# irs-v6.net
KiCad netlist of a schematic drawn in EAGLE
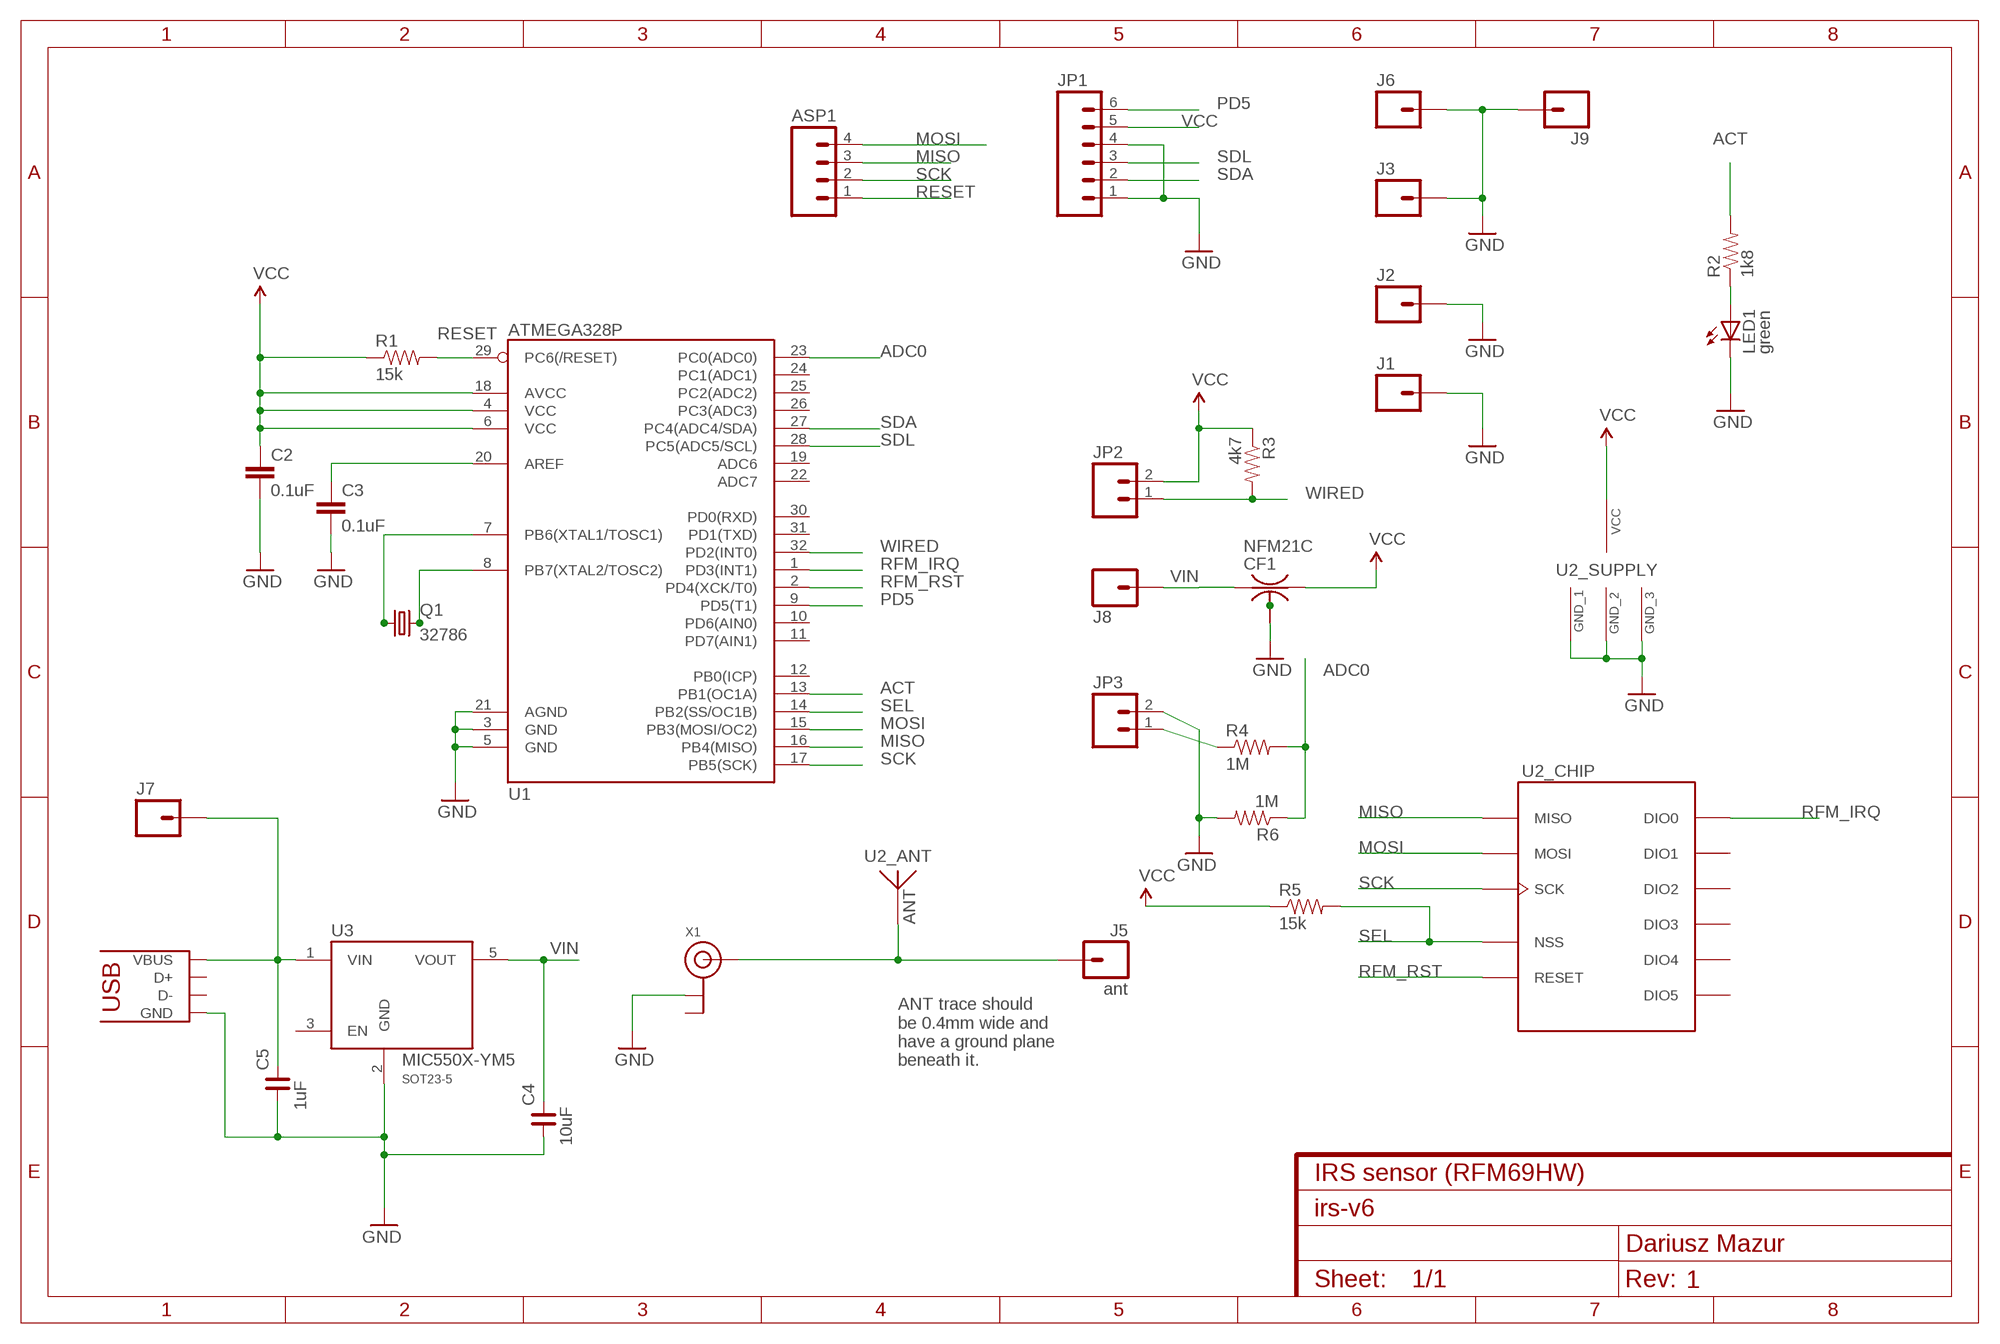
[diagram p0: schematic, sheet 1]

(export (version "E")
  (design (tool "Eeschema 10.0.6"))
  (components
    (comp (ref "ASP1")
      (value "M04NO_SILK_ALL_ROUND")
      (footprint "eagle-import:1X04_NO_SILK_ALL_ROUND")
      (libsource (lib "eagle-import") (part "M04NO_SILK_ALL_ROUND"))
    )
    (comp (ref "C2")
      (value "0.1uF")
      (footprint "eagle-import:0603-CAP")
      (libsource (lib "eagle-import") (part "0.1UF-25V(+80/-20%)(0603)"))
    )
    (comp (ref "C3")
      (value "0.1uF")
      (footprint "eagle-import:0603-CAP")
      (libsource (lib "eagle-import") (part "0.1UF-25V(+80/-20%)(0603)"))
    )
    (comp (ref "C4")
      (value "10uF")
      (footprint "eagle-import:C0805")
      (libsource (lib "eagle-import") (part "C_0805"))
    )
    (comp (ref "C5")
      (value "1uF")
      (footprint "eagle-import:C0805")
      (libsource (lib "eagle-import") (part "C_0805"))
    )
    (comp (ref "CF1")
      (value "NFM21C")
      (footprint "eagle-import:NFM21C")
      (fields (field (name "MPN") "NFM21CC102R1H3D"))
      (libsource (lib "eagle-import") (part "NFM21C"))
    )
    (comp (ref "J1")
      (value "M01PTH_NO_SILK_YES_STOP")
      (footprint "eagle-import:1X01_NO_SILK")
      (libsource (lib "eagle-import") (part "M01PTH_NO_SILK_YES_STOP"))
    )
    (comp (ref "J2")
      (value "M01PTH_NO_SILK_YES_STOP")
      (footprint "eagle-import:1X01_NO_SILK")
      (libsource (lib "eagle-import") (part "M01PTH_NO_SILK_YES_STOP"))
    )
    (comp (ref "J3")
      (value "M01PTH_NO_SILK_YES_STOP")
      (footprint "eagle-import:1X01_NO_SILK")
      (libsource (lib "eagle-import") (part "M01PTH_NO_SILK_YES_STOP"))
    )
    (comp (ref "J4")
      (value "USB-REVERSE-MICROB")
      (footprint "eagle-import:USB-MICROB")
      (libsource (lib "eagle-import") (part "USB-REVERSE-MICROB"))
    )
    (comp (ref "J5")
      (value "ant")
      (footprint "eagle-import:1X01_NO_SILK")
      (libsource (lib "eagle-import") (part "M01PTH_NO_SILK_YES_STOP"))
    )
    (comp (ref "J6")
      (value "M01PTH_NO_SILK_YES_STOP")
      (footprint "eagle-import:1X01_NO_SILK")
      (libsource (lib "eagle-import") (part "M01PTH_NO_SILK_YES_STOP"))
    )
    (comp (ref "J7")
      (value "M01PTH_NO_SILK_YES_STOP")
      (footprint "eagle-import:1X01_NO_SILK")
      (libsource (lib "eagle-import") (part "M01PTH_NO_SILK_YES_STOP"))
    )
    (comp (ref "J8")
      (value "M01PTH_NO_SILK_YES_STOP")
      (footprint "eagle-import:1X01_NO_SILK")
      (libsource (lib "eagle-import") (part "M01PTH_NO_SILK_YES_STOP"))
    )
    (comp (ref "J9")
      (value "M01PTH_NO_SILK_YES_STOP")
      (footprint "eagle-import:1X01_NO_SILK")
      (libsource (lib "eagle-import") (part "M01PTH_NO_SILK_YES_STOP"))
    )
    (comp (ref "JP1")
      (value "M06NO_SILK_FEMALE_PTH")
      (footprint "eagle-import:1X06_NO_SILK")
      (libsource (lib "eagle-import") (part "M06NO_SILK_FEMALE_PTH"))
    )
    (comp (ref "JP2")
      (value "M021X02_NO_SILK")
      (footprint "eagle-import:1X02_NO_SILK")
      (libsource (lib "eagle-import") (part "M021X02_NO_SILK"))
    )
    (comp (ref "JP3")
      (value "M021X02_NO_SILK")
      (footprint "eagle-import:1X02_NO_SILK")
      (libsource (lib "eagle-import") (part "M021X02_NO_SILK"))
    )
    (comp (ref "LED1")
      (value "green")
      (footprint "eagle-import:LED-0603")
      (libsource (lib "eagle-import") (part "LED0603"))
    )
    (comp (ref "Q1")
      (value "32786")
      (footprint "eagle-import:MC-306")
      (fields (field (name "MPN") "MC-306 60.0KHZ  100PPM ,12.5PF"))
      (libsource (lib "eagle-import") (part "MC-306"))
    )
    (comp (ref "R1")
      (value "15k")
      (footprint "eagle-import:0603-RES")
      (libsource (lib "eagle-import") (part "RESISTOR0603-RES"))
    )
    (comp (ref "R2")
      (value "1k8")
      (footprint "eagle-import:0603-RES")
      (libsource (lib "eagle-import") (part "RESISTOR0603-RES"))
    )
    (comp (ref "R3")
      (value "4k7")
      (footprint "eagle-import:0603-RES")
      (libsource (lib "eagle-import") (part "RESISTOR0603-RES"))
    )
    (comp (ref "R4")
      (value "1M")
      (footprint "eagle-import:0603-RES")
      (libsource (lib "eagle-import") (part "RESISTOR0603-RES"))
    )
    (comp (ref "R5")
      (value "15k")
      (footprint "eagle-import:0603-RES")
      (libsource (lib "eagle-import") (part "RESISTOR0603-RES"))
    )
    (comp (ref "R6")
      (value "1M")
      (footprint "eagle-import:0603-RES")
      (libsource (lib "eagle-import") (part "RESISTOR0603-RES"))
    )
    (comp (ref "U1")
      (value "ATMEGA328P")
      (footprint "eagle-import:TQFP32-08")
      (libsource (lib "eagle-import") (part "ATMEGA328_SMT"))
    )
    (comp (ref "U2")
      (value "RFM69HCW-S2")
      (footprint "eagle-import:HOPE-RF-16")
      (libsource (lib "eagle-import") (part "RFM69HCW-S2"))
    )
    (comp (ref "U3")
      (value "MIC550X-YM5")
      (footprint "eagle-import:SOT23-5-DBV")
      (libsource (lib "eagle-import") (part "MIC550X-YM5"))
    )
    (comp (ref "X1")
      (value "ANTENNA_U.FL")
      (footprint "eagle-import:U.FL")
      (libsource (lib "eagle-import") (part "ANTENNA_U.FL"))
    )
  )
  (nets
    (net (code "1") (name "/ACT") (class "Default")
      (node (ref "R2") (pin "2") (pinfunction "2_2") (pintype "passive"))
      (node (ref "U1") (pin "13") (pinfunction "PB1(OC1A)_13") (pintype "bidirectional"))
    )
    (net (code "2") (name "/ADC0") (class "Default")
      (node (ref "R4") (pin "2") (pinfunction "2_2") (pintype "passive"))
      (node (ref "R6") (pin "1") (pinfunction "1_1") (pintype "passive"))
      (node (ref "U1") (pin "23") (pinfunction "PC0(ADC0)_23") (pintype "bidirectional"))
    )
    (net (code "3") (name "/MISO") (class "Default")
      (node (ref "ASP1") (pin "3") (pinfunction "3_3") (pintype "passive"))
      (node (ref "U1") (pin "16") (pinfunction "PB4(MISO)_16") (pintype "bidirectional"))
      (node (ref "U2") (pin "MISO") (pinfunction "MISO_MISO") (pintype "input"))
    )
    (net (code "4") (name "/MOSI") (class "Default")
      (node (ref "ASP1") (pin "4") (pinfunction "4_4") (pintype "passive"))
      (node (ref "U1") (pin "15") (pinfunction "PB3(MOSI/OC2)_15") (pintype "bidirectional"))
      (node (ref "U2") (pin "MOSI") (pinfunction "MOSI_MOSI") (pintype "output"))
    )
    (net (code "5") (name "/PD5") (class "Default")
      (node (ref "JP1") (pin "6") (pinfunction "6_6") (pintype "passive"))
      (node (ref "U1") (pin "9") (pinfunction "PD5(T1)_9") (pintype "bidirectional"))
    )
    (net (code "6") (name "/RESET") (class "Default")
      (node (ref "ASP1") (pin "1") (pinfunction "1_1") (pintype "passive"))
      (node (ref "R1") (pin "2") (pinfunction "2_2") (pintype "passive"))
      (node (ref "U1") (pin "29") (pinfunction "PC6(/RESET)_29") (pintype "bidirectional"))
    )
    (net (code "7") (name "/RFM_IRQ") (class "Default")
      (node (ref "U1") (pin "1") (pinfunction "PD3(INT1)_1") (pintype "bidirectional"))
      (node (ref "U2") (pin "DIO0") (pinfunction "DIO0_DIO0") (pintype "bidirectional"))
    )
    (net (code "8") (name "/RFM_RST") (class "Default")
      (node (ref "U1") (pin "2") (pinfunction "PD4(XCK/T0)_2") (pintype "bidirectional"))
      (node (ref "U2") (pin "RESET") (pinfunction "RESET_RESET") (pintype "bidirectional"))
    )
    (net (code "9") (name "/SCK") (class "Default")
      (node (ref "ASP1") (pin "2") (pinfunction "2_2") (pintype "passive"))
      (node (ref "U1") (pin "17") (pinfunction "PB5(SCK)_17") (pintype "bidirectional"))
      (node (ref "U2") (pin "SCK") (pinfunction "SCK_SCK") (pintype "input"))
    )
    (net (code "10") (name "/SDA") (class "Default")
      (node (ref "JP1") (pin "2") (pinfunction "2_2") (pintype "passive"))
      (node (ref "U1") (pin "27") (pinfunction "PC4(ADC4/SDA)_27") (pintype "bidirectional"))
    )
    (net (code "11") (name "/SDL") (class "Default")
      (node (ref "JP1") (pin "3") (pinfunction "3_3") (pintype "passive"))
      (node (ref "U1") (pin "28") (pinfunction "PC5(ADC5/SCL)_28") (pintype "bidirectional"))
    )
    (net (code "12") (name "/SEL") (class "Default")
      (node (ref "R5") (pin "2") (pinfunction "2_2") (pintype "passive"))
      (node (ref "U1") (pin "14") (pinfunction "PB2(SS/OC1B)_14") (pintype "bidirectional"))
      (node (ref "U2") (pin "NSS") (pinfunction "NSS_NSS") (pintype "input"))
    )
    (net (code "13") (name "/VIN") (class "Default")
      (node (ref "C4") (pin "2") (pinfunction "2_2") (pintype "passive"))
      (node (ref "CF1") (pin "1") (pinfunction "1_1") (pintype "passive"))
      (node (ref "J8") (pin "1") (pinfunction "1_1") (pintype "passive"))
      (node (ref "U3") (pin "5") (pinfunction "VOUT_5") (pintype "bidirectional"))
    )
    (net (code "14") (name "/WIRED") (class "Default")
      (node (ref "JP2") (pin "1") (pinfunction "1_1") (pintype "passive"))
      (node (ref "R3") (pin "2") (pinfunction "2_2") (pintype "passive"))
      (node (ref "U1") (pin "32") (pinfunction "PD2(INT0)_32") (pintype "bidirectional"))
    )
    (net (code "15") (name "GND") (class "Default")
      (node (ref "C2") (pin "2") (pinfunction "2_2") (pintype "passive"))
      (node (ref "C3") (pin "2") (pinfunction "2_2") (pintype "passive"))
      (node (ref "C4") (pin "1") (pinfunction "1_1") (pintype "passive"))
      (node (ref "C5") (pin "1") (pinfunction "1_1") (pintype "passive"))
      (node (ref "CF1") (pin "2@1") (pinfunction "2_2@1") (pintype "passive"))
      (node (ref "J1") (pin "1") (pinfunction "1_1") (pintype "passive"))
      (node (ref "J2") (pin "1") (pinfunction "1_1") (pintype "passive"))
      (node (ref "J3") (pin "1") (pinfunction "1_1") (pintype "passive"))
      (node (ref "J4") (pin "MT1") (pinfunction "GND_MT1") (pintype "bidirectional"))
      (node (ref "J4") (pin "MT2") (pinfunction "GND_MT2") (pintype "bidirectional"))
      (node (ref "J4") (pin "VBUS") (pinfunction "GND_VBUS") (pintype "bidirectional"))
      (node (ref "J6") (pin "1") (pinfunction "1_1") (pintype "passive"))
      (node (ref "J9") (pin "1") (pinfunction "1_1") (pintype "passive"))
      (node (ref "JP1") (pin "1") (pinfunction "1_1") (pintype "passive"))
      (node (ref "JP1") (pin "4") (pinfunction "4_4") (pintype "passive"))
      (node (ref "JP3") (pin "2") (pinfunction "2_2") (pintype "passive"))
      (node (ref "LED1") (pin "C") (pinfunction "C_C") (pintype "passive"))
      (node (ref "R6") (pin "2") (pinfunction "2_2") (pintype "passive"))
      (node (ref "U1") (pin "21") (pinfunction "AGND_21") (pintype "bidirectional"))
      (node (ref "U1") (pin "3") (pinfunction "GND_3") (pintype "bidirectional"))
      (node (ref "U1") (pin "5") (pinfunction "GND_5") (pintype "bidirectional"))
      (node (ref "U2") (pin "GND1") (pinfunction "GND_1_GND1") (pintype "power_in"))
      (node (ref "U2") (pin "GND2") (pinfunction "GND_2_GND2") (pintype "power_in"))
      (node (ref "U2") (pin "GND3") (pinfunction "GND_3_GND3") (pintype "power_in"))
      (node (ref "U3") (pin "2") (pinfunction "GND_2") (pintype "bidirectional"))
      (node (ref "X1") (pin "1") (pinfunction "GND_1") (pintype "passive"))
    )
    (net (code "16") (name "Net-(J4-VBUS)") (class "Default")
      (node (ref "C5") (pin "2") (pinfunction "2_2") (pintype "passive"))
      (node (ref "J4") (pin "GND") (pinfunction "VBUS_GND") (pintype "bidirectional"))
      (node (ref "J7") (pin "1") (pinfunction "1_1") (pintype "passive"))
      (node (ref "U3") (pin "1") (pinfunction "VIN_1") (pintype "bidirectional"))
    )
    (net (code "17") (name "Net-(JP3-Pad1)") (class "Default")
      (node (ref "JP3") (pin "1") (pinfunction "1_1") (pintype "passive"))
      (node (ref "R4") (pin "1") (pinfunction "1_1") (pintype "passive"))
    )
    (net (code "18") (name "Net-(LED1-PadA)") (class "Default")
      (node (ref "LED1") (pin "A") (pinfunction "A_A") (pintype "passive"))
      (node (ref "R2") (pin "1") (pinfunction "1_1") (pintype "passive"))
    )
    (net (code "19") (name "Net-(Q1-2)") (class "Default")
      (node (ref "Q1") (pin "4") (pinfunction "2_4") (pintype "passive"))
      (node (ref "U1") (pin "8") (pinfunction "PB7(XTAL2/TOSC2)_8") (pintype "bidirectional"))
    )
    (net (code "20") (name "Net-(U1-AREF)") (class "Default")
      (node (ref "C3") (pin "1") (pinfunction "1_1") (pintype "passive"))
      (node (ref "U1") (pin "20") (pinfunction "AREF_20") (pintype "bidirectional"))
    )
    (net (code "21") (name "Net-(U1-PB6(XTAL1{slash}TOSC1))") (class "Default")
      (node (ref "Q1") (pin "1") (pinfunction "1_1") (pintype "passive"))
      (node (ref "U1") (pin "7") (pinfunction "PB6(XTAL1/TOSC1)_7") (pintype "bidirectional"))
    )
    (net (code "22") (name "Net-(X1-SIGNAL)") (class "Default")
      (node (ref "J5") (pin "1") (pinfunction "1_1") (pintype "passive"))
      (node (ref "U2") (pin "ANT") (pinfunction "ANT_ANT") (pintype "passive"))
      (node (ref "X1") (pin "3") (pinfunction "SIGNAL_3") (pintype "passive"))
    )
    (net (code "23") (name "VCC") (class "Default")
      (node (ref "C2") (pin "1") (pinfunction "1_1") (pintype "passive"))
      (node (ref "CF1") (pin "3") (pinfunction "3_3") (pintype "passive"))
      (node (ref "JP1") (pin "5") (pinfunction "5_5") (pintype "passive"))
      (node (ref "JP2") (pin "2") (pinfunction "2_2") (pintype "passive"))
      (node (ref "R1") (pin "1") (pinfunction "1_1") (pintype "passive"))
      (node (ref "R3") (pin "1") (pinfunction "1_1") (pintype "passive"))
      (node (ref "R5") (pin "1") (pinfunction "1_1") (pintype "passive"))
      (node (ref "U1") (pin "18") (pinfunction "AVCC_18") (pintype "bidirectional"))
      (node (ref "U1") (pin "4") (pinfunction "VCC_4") (pintype "bidirectional"))
      (node (ref "U1") (pin "6") (pinfunction "VCC_6") (pintype "bidirectional"))
      (node (ref "U2") (pin "3.3V") (pinfunction "VCC_3.3V") (pintype "power_in"))
    )
    (net (code "24") (name "unconnected-(CF1-2-Pad2@2)") (class "Default")
      (node (ref "CF1") (pin "2@2") (pinfunction "2_2@2") (pintype "passive"))
    )
    (net (code "25") (name "unconnected-(J4-D--PadID)") (class "Default")
      (node (ref "J4") (pin "ID") (pinfunction "D-_ID") (pintype "bidirectional"))
    )
    (net (code "26") (name "unconnected-(J4-PadD+)") (class "Default")
      (node (ref "J4") (pin "D+") (pinfunction "D+_D+") (pintype "bidirectional"))
    )
    (net (code "27") (name "unconnected-(U1-ADC6-Pad19)") (class "Default")
      (node (ref "U1") (pin "19") (pinfunction "ADC6_19") (pintype "bidirectional"))
    )
    (net (code "28") (name "unconnected-(U1-ADC7-Pad22)") (class "Default")
      (node (ref "U1") (pin "22") (pinfunction "ADC7_22") (pintype "bidirectional"))
    )
    (net (code "29") (name "unconnected-(U1-PB0(ICP)-Pad12)") (class "Default")
      (node (ref "U1") (pin "12") (pinfunction "PB0(ICP)_12") (pintype "bidirectional"))
    )
    (net (code "30") (name "unconnected-(U1-PC1(ADC1)-Pad24)") (class "Default")
      (node (ref "U1") (pin "24") (pinfunction "PC1(ADC1)_24") (pintype "bidirectional"))
    )
    (net (code "31") (name "unconnected-(U1-PC2(ADC2)-Pad25)") (class "Default")
      (node (ref "U1") (pin "25") (pinfunction "PC2(ADC2)_25") (pintype "bidirectional"))
    )
    (net (code "32") (name "unconnected-(U1-PC3(ADC3)-Pad26)") (class "Default")
      (node (ref "U1") (pin "26") (pinfunction "PC3(ADC3)_26") (pintype "bidirectional"))
    )
    (net (code "33") (name "unconnected-(U1-PD0(RXD)-Pad30)") (class "Default")
      (node (ref "U1") (pin "30") (pinfunction "PD0(RXD)_30") (pintype "bidirectional"))
    )
    (net (code "34") (name "unconnected-(U1-PD1(TXD)-Pad31)") (class "Default")
      (node (ref "U1") (pin "31") (pinfunction "PD1(TXD)_31") (pintype "bidirectional"))
    )
    (net (code "35") (name "unconnected-(U1-PD6(AIN0)-Pad10)") (class "Default")
      (node (ref "U1") (pin "10") (pinfunction "PD6(AIN0)_10") (pintype "bidirectional"))
    )
    (net (code "36") (name "unconnected-(U1-PD7(AIN1)-Pad11)") (class "Default")
      (node (ref "U1") (pin "11") (pinfunction "PD7(AIN1)_11") (pintype "bidirectional"))
    )
    (net (code "37") (name "unconnected-(U2-PadDIO1)") (class "Default")
      (node (ref "U2") (pin "DIO1") (pinfunction "DIO1_DIO1") (pintype "bidirectional"))
    )
    (net (code "38") (name "unconnected-(U2-PadDIO2)") (class "Default")
      (node (ref "U2") (pin "DIO2") (pinfunction "DIO2_DIO2") (pintype "bidirectional"))
    )
    (net (code "39") (name "unconnected-(U2-PadDIO3)") (class "Default")
      (node (ref "U2") (pin "DIO3") (pinfunction "DIO3_DIO3") (pintype "bidirectional"))
    )
    (net (code "40") (name "unconnected-(U2-PadDIO4)") (class "Default")
      (node (ref "U2") (pin "DIO4") (pinfunction "DIO4_DIO4") (pintype "bidirectional"))
    )
    (net (code "41") (name "unconnected-(U2-PadDIO5)") (class "Default")
      (node (ref "U2") (pin "DIO5") (pinfunction "DIO5_DIO5") (pintype "bidirectional"))
    )
    (net (code "42") (name "unconnected-(U3-EN-Pad3)") (class "Default")
      (node (ref "U3") (pin "3") (pinfunction "EN_3") (pintype "bidirectional"))
    )
    (net (code "43") (name "unconnected-(X1-GND-Pad2)") (class "Default")
      (node (ref "X1") (pin "2") (pinfunction "GND_2") (pintype "passive"))
    )
  )
)
